# BPF.net
KiCad netlist of a schematic drawn in EAGLE
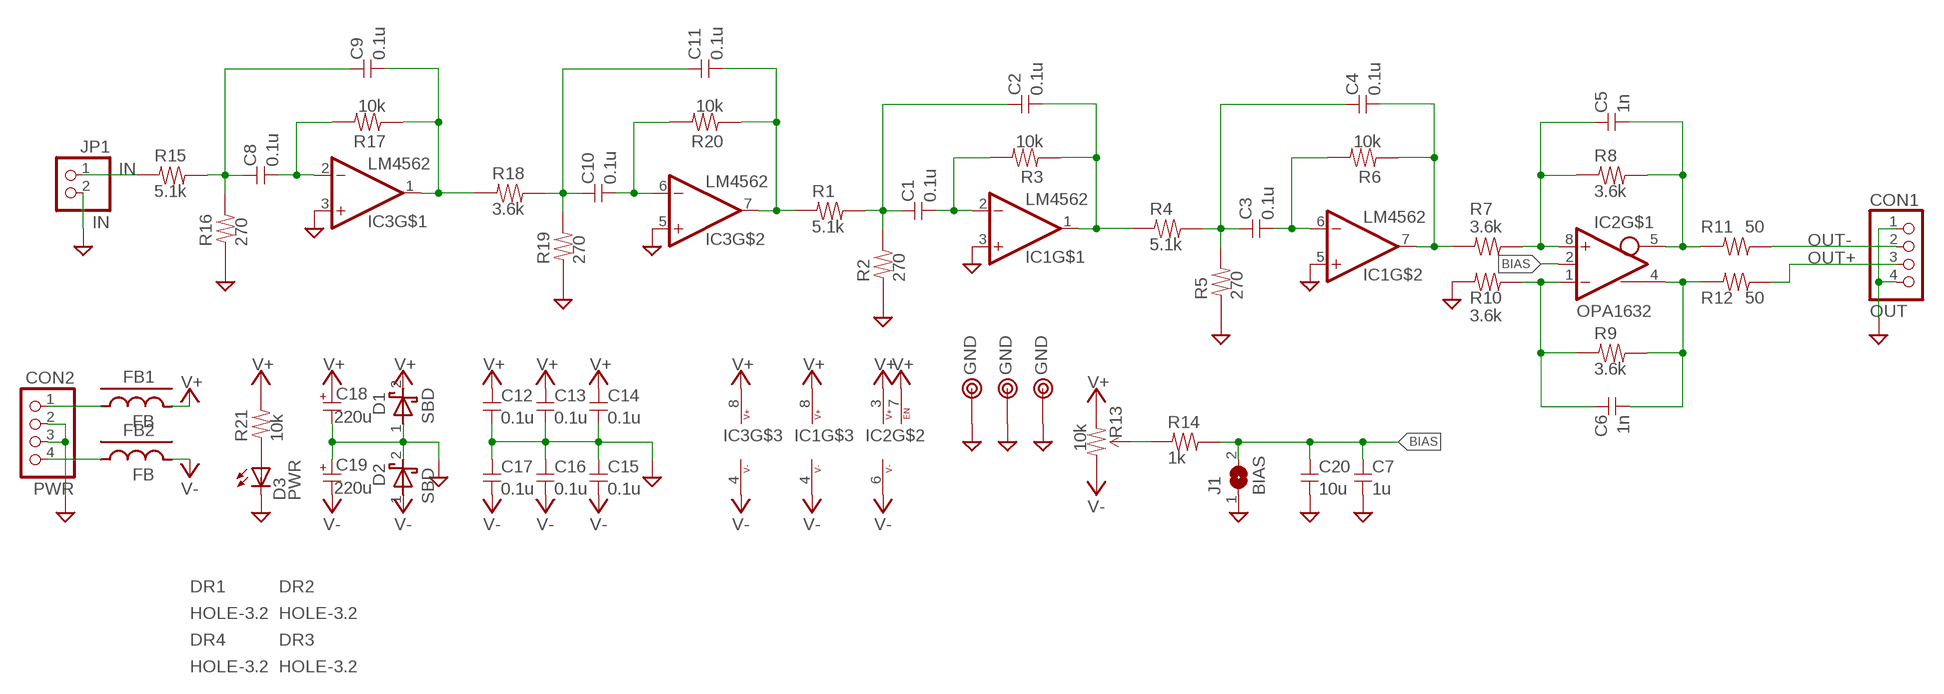
[diagram p0: schematic, sheet 1]

(export (version "E")
  (design (tool "Eeschema 10.0.6"))
  (components
    (comp (ref "C1")
      (value "0.1u")
      (footprint "eagle-import:C050W")
      (libsource (lib "eagle-import") (part "C-5W"))
    )
    (comp (ref "C2")
      (value "0.1u")
      (footprint "eagle-import:C050W")
      (libsource (lib "eagle-import") (part "C-5W"))
    )
    (comp (ref "C3")
      (value "0.1u")
      (footprint "eagle-import:C050W")
      (libsource (lib "eagle-import") (part "C-5W"))
    )
    (comp (ref "C4")
      (value "0.1u")
      (footprint "eagle-import:C050W")
      (libsource (lib "eagle-import") (part "C-5W"))
    )
    (comp (ref "C5")
      (value "1n")
      (footprint "eagle-import:2012")
      (libsource (lib "eagle-import") (part "C-2012"))
    )
    (comp (ref "C6")
      (value "1n")
      (footprint "eagle-import:2012")
      (libsource (lib "eagle-import") (part "C-2012"))
    )
    (comp (ref "C7")
      (value "1u")
      (footprint "eagle-import:1608C")
      (libsource (lib "eagle-import") (part "C-1608"))
    )
    (comp (ref "C8")
      (value "0.1u")
      (footprint "eagle-import:C050W")
      (libsource (lib "eagle-import") (part "C-5W"))
    )
    (comp (ref "C9")
      (value "0.1u")
      (footprint "eagle-import:C050W")
      (libsource (lib "eagle-import") (part "C-5W"))
    )
    (comp (ref "C10")
      (value "0.1u")
      (footprint "eagle-import:C050W")
      (libsource (lib "eagle-import") (part "C-5W"))
    )
    (comp (ref "C11")
      (value "0.1u")
      (footprint "eagle-import:C050W")
      (libsource (lib "eagle-import") (part "C-5W"))
    )
    (comp (ref "C12")
      (value "0.1u")
      (footprint "eagle-import:1608C")
      (libsource (lib "eagle-import") (part "C-1608"))
    )
    (comp (ref "C13")
      (value "0.1u")
      (footprint "eagle-import:1608C")
      (libsource (lib "eagle-import") (part "C-1608"))
    )
    (comp (ref "C14")
      (value "0.1u")
      (footprint "eagle-import:1608C")
      (libsource (lib "eagle-import") (part "C-1608"))
    )
    (comp (ref "C15")
      (value "0.1u")
      (footprint "eagle-import:1608C")
      (libsource (lib "eagle-import") (part "C-1608"))
    )
    (comp (ref "C16")
      (value "0.1u")
      (footprint "eagle-import:1608C")
      (libsource (lib "eagle-import") (part "C-1608"))
    )
    (comp (ref "C17")
      (value "0.1u")
      (footprint "eagle-import:1608C")
      (libsource (lib "eagle-import") (part "C-1608"))
    )
    (comp (ref "C18")
      (value "220u")
      (footprint "eagle-import:E2,5-8")
      (libsource (lib "eagle-import") (part "CPOLE2.5-8"))
    )
    (comp (ref "C19")
      (value "220u")
      (footprint "eagle-import:E2,5-8")
      (libsource (lib "eagle-import") (part "CPOLE2.5-8"))
    )
    (comp (ref "C20")
      (value "10u")
      (footprint "eagle-import:3216")
      (libsource (lib "eagle-import") (part "C-3216"))
    )
    (comp (ref "CON1")
      (value "OUT")
      (footprint "eagle-import:1X04")
      (libsource (lib "eagle-import") (part "PINHD-1X4-N"))
    )
    (comp (ref "CON2")
      (value "PWR")
      (footprint "eagle-import:1X04")
      (libsource (lib "eagle-import") (part "PINHD-1X4-N"))
    )
    (comp (ref "D1")
      (value "SBD")
      (footprint "eagle-import:SOD123")
      (libsource (lib "eagle-import") (part "SBD-1A2"))
    )
    (comp (ref "D2")
      (value "SBD")
      (footprint "eagle-import:SOD123")
      (libsource (lib "eagle-import") (part "SBD-1A2"))
    )
    (comp (ref "D3")
      (value "PWR")
      (footprint "eagle-import:D1608")
      (libsource (lib "eagle-import") (part "LED-SMD1608"))
    )
    (comp (ref "DR1")
      (value "HOLE-3.2")
      (footprint "eagle-import:HOLE_3.2")
      (libsource (lib "eagle-import") (part "HOLE-3.2"))
    )
    (comp (ref "DR2")
      (value "HOLE-3.2")
      (footprint "eagle-import:HOLE_3.2")
      (libsource (lib "eagle-import") (part "HOLE-3.2"))
    )
    (comp (ref "DR3")
      (value "HOLE-3.2")
      (footprint "eagle-import:HOLE_3.2")
      (libsource (lib "eagle-import") (part "HOLE-3.2"))
    )
    (comp (ref "DR4")
      (value "HOLE-3.2")
      (footprint "eagle-import:HOLE_3.2")
      (libsource (lib "eagle-import") (part "HOLE-3.2"))
    )
    (comp (ref "FB1")
      (value "FB")
      (footprint "eagle-import:2012-R")
      (libsource (lib "eagle-import") (part "FB-2012-FB"))
    )
    (comp (ref "FB2")
      (value "FB")
      (footprint "eagle-import:2012-R")
      (libsource (lib "eagle-import") (part "FB-2012-FB"))
    )
    (comp (ref "IC1")
      (value "LM4562")
      (footprint "eagle-import:SOP8")
      (libsource (lib "eagle-import") (part "OPA-2-SOP"))
    )
    (comp (ref "IC2")
      (value "OPA1632")
      (footprint "eagle-import:SOP8")
      (libsource (lib "eagle-import") (part "OPA-DIFF"))
    )
    (comp (ref "IC3")
      (value "LM4562")
      (footprint "eagle-import:SOP8")
      (libsource (lib "eagle-import") (part "OPA-2-SOP"))
    )
    (comp (ref "J1")
      (value "BIAS")
      (footprint "eagle-import:1608-J")
      (libsource (lib "eagle-import") (part "SJ-1608"))
    )
    (comp (ref "JP1")
      (value "IN")
      (footprint "eagle-import:1X02")
      (libsource (lib "eagle-import") (part "PINHD-1X2"))
    )
    (comp (ref "R1")
      (value "5.1k")
      (footprint "eagle-import:2012")
      (libsource (lib "eagle-import") (part "R-2012"))
    )
    (comp (ref "R2")
      (value "270")
      (footprint "eagle-import:2012")
      (libsource (lib "eagle-import") (part "R-2012"))
    )
    (comp (ref "R3")
      (value "10k")
      (footprint "eagle-import:2012")
      (libsource (lib "eagle-import") (part "R-2012"))
    )
    (comp (ref "R4")
      (value "5.1k")
      (footprint "eagle-import:2012")
      (libsource (lib "eagle-import") (part "R-2012"))
    )
    (comp (ref "R5")
      (value "270")
      (footprint "eagle-import:2012")
      (libsource (lib "eagle-import") (part "R-2012"))
    )
    (comp (ref "R6")
      (value "10k")
      (footprint "eagle-import:2012")
      (libsource (lib "eagle-import") (part "R-2012"))
    )
    (comp (ref "R7")
      (value "3.6k")
      (footprint "eagle-import:2012")
      (libsource (lib "eagle-import") (part "R-2012"))
    )
    (comp (ref "R8")
      (value "3.6k")
      (footprint "eagle-import:2012")
      (libsource (lib "eagle-import") (part "R-2012"))
    )
    (comp (ref "R9")
      (value "3.6k")
      (footprint "eagle-import:2012")
      (libsource (lib "eagle-import") (part "R-2012"))
    )
    (comp (ref "R10")
      (value "3.6k")
      (footprint "eagle-import:2012")
      (libsource (lib "eagle-import") (part "R-2012"))
    )
    (comp (ref "R11")
      (value "50")
      (footprint "eagle-import:1608")
      (libsource (lib "eagle-import") (part "R-1608"))
    )
    (comp (ref "R12")
      (value "50")
      (footprint "eagle-import:1608")
      (libsource (lib "eagle-import") (part "R-1608"))
    )
    (comp (ref "R13")
      (value "10k")
      (footprint "eagle-import:3296W")
      (libsource (lib "eagle-import") (part "R-VAL-3296W"))
    )
    (comp (ref "R14")
      (value "1k")
      (footprint "eagle-import:1608")
      (libsource (lib "eagle-import") (part "R-1608"))
    )
    (comp (ref "R15")
      (value "5.1k")
      (footprint "eagle-import:2012")
      (libsource (lib "eagle-import") (part "R-2012"))
    )
    (comp (ref "R16")
      (value "270")
      (footprint "eagle-import:2012")
      (libsource (lib "eagle-import") (part "R-2012"))
    )
    (comp (ref "R17")
      (value "10k")
      (footprint "eagle-import:2012")
      (libsource (lib "eagle-import") (part "R-2012"))
    )
    (comp (ref "R18")
      (value "3.6k")
      (footprint "eagle-import:2012")
      (libsource (lib "eagle-import") (part "R-2012"))
    )
    (comp (ref "R19")
      (value "270")
      (footprint "eagle-import:2012")
      (libsource (lib "eagle-import") (part "R-2012"))
    )
    (comp (ref "R20")
      (value "10k")
      (footprint "eagle-import:2012")
      (libsource (lib "eagle-import") (part "R-2012"))
    )
    (comp (ref "R21")
      (value "10k")
      (footprint "eagle-import:1608")
      (libsource (lib "eagle-import") (part "R-1608"))
    )
    (comp (ref "TP1")
      (value "GND")
      (footprint "eagle-import:TESTPIN")
      (libsource (lib "eagle-import") (part "TESTPIN"))
    )
    (comp (ref "TP2")
      (value "GND")
      (footprint "eagle-import:TESTPIN")
      (libsource (lib "eagle-import") (part "TESTPIN"))
    )
    (comp (ref "TP3")
      (value "GND")
      (footprint "eagle-import:TESTPIN")
      (libsource (lib "eagle-import") (part "TESTPIN"))
    )
  )
  (nets
    (net (code "1") (name "/IN") (class "Default")
      (node (ref "JP1") (pin "1") (pinfunction "1_1") (pintype "passive"))
      (node (ref "R15") (pin "1") (pinfunction "1_1") (pintype "passive"))
    )
    (net (code "2") (name "/OUT+") (class "Default")
      (node (ref "CON1") (pin "3") (pinfunction "3_3") (pintype "passive"))
      (node (ref "R12") (pin "2") (pinfunction "2_2") (pintype "passive"))
    )
    (net (code "3") (name "/OUT-") (class "Default")
      (node (ref "CON1") (pin "2") (pinfunction "2_2") (pintype "passive"))
      (node (ref "R11") (pin "2") (pinfunction "2_2") (pintype "passive"))
    )
    (net (code "4") (name "BIAS") (class "Default")
      (node (ref "C20") (pin "1") (pinfunction "1_1") (pintype "passive"))
      (node (ref "C7") (pin "1") (pinfunction "1_1") (pintype "passive"))
      (node (ref "IC2") (pin "2") (pinfunction "CM_2") (pintype "input"))
      (node (ref "J1") (pin "2") (pinfunction "2_2") (pintype "passive"))
      (node (ref "R14") (pin "2") (pinfunction "2_2") (pintype "passive"))
    )
    (net (code "5") (name "GND") (class "Default")
      (node (ref "C12") (pin "2") (pinfunction "2_2") (pintype "passive"))
      (node (ref "C13") (pin "2") (pinfunction "2_2") (pintype "passive"))
      (node (ref "C14") (pin "2") (pinfunction "2_2") (pintype "passive"))
      (node (ref "C15") (pin "1") (pinfunction "1_1") (pintype "passive"))
      (node (ref "C16") (pin "1") (pinfunction "1_1") (pintype "passive"))
      (node (ref "C17") (pin "1") (pinfunction "1_1") (pintype "passive"))
      (node (ref "C18") (pin "-") (pinfunction "2_-") (pintype "passive"))
      (node (ref "C19") (pin "+") (pinfunction "1_+") (pintype "passive"))
      (node (ref "C20") (pin "2") (pinfunction "2_2") (pintype "passive"))
      (node (ref "C7") (pin "2") (pinfunction "2_2") (pintype "passive"))
      (node (ref "CON1") (pin "1") (pinfunction "1_1") (pintype "passive"))
      (node (ref "CON1") (pin "4") (pinfunction "4_4") (pintype "passive"))
      (node (ref "CON2") (pin "2") (pinfunction "2_2") (pintype "passive"))
      (node (ref "CON2") (pin "3") (pinfunction "3_3") (pintype "passive"))
      (node (ref "D1") (pin "1") (pinfunction "A_1") (pintype "bidirectional"))
      (node (ref "D2") (pin "2") (pinfunction "K_2") (pintype "bidirectional"))
      (node (ref "D3") (pin "K") (pinfunction "K_K") (pintype "passive"))
      (node (ref "IC1") (pin "3") (pinfunction "+IN_3") (pintype "input"))
      (node (ref "IC1") (pin "5") (pinfunction "+IN_5") (pintype "input"))
      (node (ref "IC3") (pin "3") (pinfunction "+IN_3") (pintype "input"))
      (node (ref "IC3") (pin "5") (pinfunction "+IN_5") (pintype "input"))
      (node (ref "J1") (pin "1") (pinfunction "1_1") (pintype "passive"))
      (node (ref "JP1") (pin "2") (pinfunction "2_2") (pintype "passive"))
      (node (ref "R10") (pin "1") (pinfunction "1_1") (pintype "passive"))
      (node (ref "R16") (pin "1") (pinfunction "1_1") (pintype "passive"))
      (node (ref "R19") (pin "1") (pinfunction "1_1") (pintype "passive"))
      (node (ref "R2") (pin "1") (pinfunction "1_1") (pintype "passive"))
      (node (ref "R5") (pin "1") (pinfunction "1_1") (pintype "passive"))
      (node (ref "TP1") (pin "1") (pinfunction "1_1") (pintype "passive"))
      (node (ref "TP2") (pin "1") (pinfunction "1_1") (pintype "passive"))
      (node (ref "TP3") (pin "1") (pinfunction "1_1") (pintype "passive"))
    )
    (net (code "6") (name "Net-(C1-1-Pad3)") (class "Default")
      (node (ref "C1") (pin "1") (pinfunction "1_1") (pintype "passive"))
      (node (ref "C1") (pin "3") (pinfunction "1_3") (pintype "passive"))
      (node (ref "C2") (pin "1") (pinfunction "1_1") (pintype "passive"))
      (node (ref "C2") (pin "3") (pinfunction "1_3") (pintype "passive"))
      (node (ref "R1") (pin "2") (pinfunction "2_2") (pintype "passive"))
      (node (ref "R2") (pin "2") (pinfunction "2_2") (pintype "passive"))
    )
    (net (code "7") (name "Net-(C3-1-Pad3)") (class "Default")
      (node (ref "C3") (pin "1") (pinfunction "1_1") (pintype "passive"))
      (node (ref "C3") (pin "3") (pinfunction "1_3") (pintype "passive"))
      (node (ref "C4") (pin "1") (pinfunction "1_1") (pintype "passive"))
      (node (ref "C4") (pin "3") (pinfunction "1_3") (pintype "passive"))
      (node (ref "R4") (pin "2") (pinfunction "2_2") (pintype "passive"))
      (node (ref "R5") (pin "2") (pinfunction "2_2") (pintype "passive"))
    )
    (net (code "8") (name "Net-(C8-1-Pad3)") (class "Default")
      (node (ref "C8") (pin "1") (pinfunction "1_1") (pintype "passive"))
      (node (ref "C8") (pin "3") (pinfunction "1_3") (pintype "passive"))
      (node (ref "C9") (pin "1") (pinfunction "1_1") (pintype "passive"))
      (node (ref "C9") (pin "3") (pinfunction "1_3") (pintype "passive"))
      (node (ref "R15") (pin "2") (pinfunction "2_2") (pintype "passive"))
      (node (ref "R16") (pin "2") (pinfunction "2_2") (pintype "passive"))
    )
    (net (code "9") (name "Net-(C10-1-Pad3)") (class "Default")
      (node (ref "C10") (pin "1") (pinfunction "1_1") (pintype "passive"))
      (node (ref "C10") (pin "3") (pinfunction "1_3") (pintype "passive"))
      (node (ref "C11") (pin "1") (pinfunction "1_1") (pintype "passive"))
      (node (ref "C11") (pin "3") (pinfunction "1_3") (pintype "passive"))
      (node (ref "R18") (pin "2") (pinfunction "2_2") (pintype "passive"))
      (node (ref "R19") (pin "2") (pinfunction "2_2") (pintype "passive"))
    )
    (net (code "10") (name "Net-(CON2-Pad1)") (class "Default")
      (node (ref "CON2") (pin "1") (pinfunction "1_1") (pintype "passive"))
      (node (ref "FB1") (pin "1") (pinfunction "1_1") (pintype "passive"))
    )
    (net (code "11") (name "Net-(CON2-Pad4)") (class "Default")
      (node (ref "CON2") (pin "4") (pinfunction "4_4") (pintype "passive"))
      (node (ref "FB2") (pin "1") (pinfunction "1_1") (pintype "passive"))
    )
    (net (code "12") (name "Net-(D3-PadA)") (class "Default")
      (node (ref "D3") (pin "A") (pinfunction "A_A") (pintype "passive"))
      (node (ref "R21") (pin "1") (pinfunction "1_1") (pintype "passive"))
    )
    (net (code "13") (name "Net-(IC1A--IN)") (class "Default")
      (node (ref "C1") (pin "2") (pinfunction "2_2") (pintype "passive"))
      (node (ref "C1") (pin "4") (pinfunction "2_4") (pintype "passive"))
      (node (ref "IC1") (pin "2") (pinfunction "-IN_2") (pintype "input"))
      (node (ref "R3") (pin "2") (pinfunction "2_2") (pintype "passive"))
    )
    (net (code "14") (name "Net-(IC1A-OUT)") (class "Default")
      (node (ref "C2") (pin "2") (pinfunction "2_2") (pintype "passive"))
      (node (ref "C2") (pin "4") (pinfunction "2_4") (pintype "passive"))
      (node (ref "IC1") (pin "1") (pinfunction "OUT_1") (pintype "output"))
      (node (ref "R3") (pin "1") (pinfunction "1_1") (pintype "passive"))
      (node (ref "R4") (pin "1") (pinfunction "1_1") (pintype "passive"))
    )
    (net (code "15") (name "Net-(IC1B--IN)") (class "Default")
      (node (ref "C3") (pin "2") (pinfunction "2_2") (pintype "passive"))
      (node (ref "C3") (pin "4") (pinfunction "2_4") (pintype "passive"))
      (node (ref "IC1") (pin "6") (pinfunction "-IN_6") (pintype "input"))
      (node (ref "R6") (pin "2") (pinfunction "2_2") (pintype "passive"))
    )
    (net (code "16") (name "Net-(IC1B-OUT)") (class "Default")
      (node (ref "C4") (pin "2") (pinfunction "2_2") (pintype "passive"))
      (node (ref "C4") (pin "4") (pinfunction "2_4") (pintype "passive"))
      (node (ref "IC1") (pin "7") (pinfunction "OUT_7") (pintype "output"))
      (node (ref "R6") (pin "1") (pinfunction "1_1") (pintype "passive"))
      (node (ref "R7") (pin "1") (pinfunction "1_1") (pintype "passive"))
    )
    (net (code "17") (name "Net-(IC2A-+IN)") (class "Default")
      (node (ref "C5") (pin "1") (pinfunction "1_1") (pintype "passive"))
      (node (ref "IC2") (pin "8") (pinfunction "+IN_8") (pintype "input"))
      (node (ref "R7") (pin "2") (pinfunction "2_2") (pintype "passive"))
      (node (ref "R8") (pin "1") (pinfunction "1_1") (pintype "passive"))
    )
    (net (code "18") (name "Net-(IC2A-+OUT)") (class "Default")
      (node (ref "C6") (pin "2") (pinfunction "2_2") (pintype "passive"))
      (node (ref "IC2") (pin "4") (pinfunction "+OUT_4") (pintype "output"))
      (node (ref "R12") (pin "1") (pinfunction "1_1") (pintype "passive"))
      (node (ref "R9") (pin "2") (pinfunction "2_2") (pintype "passive"))
    )
    (net (code "19") (name "Net-(IC2A--IN)") (class "Default")
      (node (ref "C6") (pin "1") (pinfunction "1_1") (pintype "passive"))
      (node (ref "IC2") (pin "1") (pinfunction "-IN_1") (pintype "input"))
      (node (ref "R10") (pin "2") (pinfunction "2_2") (pintype "passive"))
      (node (ref "R9") (pin "1") (pinfunction "1_1") (pintype "passive"))
    )
    (net (code "20") (name "Net-(IC2A--OUT)") (class "Default")
      (node (ref "C5") (pin "2") (pinfunction "2_2") (pintype "passive"))
      (node (ref "IC2") (pin "5") (pinfunction "-OUT_5") (pintype "output"))
      (node (ref "R11") (pin "1") (pinfunction "1_1") (pintype "passive"))
      (node (ref "R8") (pin "2") (pinfunction "2_2") (pintype "passive"))
    )
    (net (code "21") (name "Net-(IC3A--IN)") (class "Default")
      (node (ref "C8") (pin "2") (pinfunction "2_2") (pintype "passive"))
      (node (ref "C8") (pin "4") (pinfunction "2_4") (pintype "passive"))
      (node (ref "IC3") (pin "2") (pinfunction "-IN_2") (pintype "input"))
      (node (ref "R17") (pin "2") (pinfunction "2_2") (pintype "passive"))
    )
    (net (code "22") (name "Net-(IC3A-OUT)") (class "Default")
      (node (ref "C9") (pin "2") (pinfunction "2_2") (pintype "passive"))
      (node (ref "C9") (pin "4") (pinfunction "2_4") (pintype "passive"))
      (node (ref "IC3") (pin "1") (pinfunction "OUT_1") (pintype "output"))
      (node (ref "R17") (pin "1") (pinfunction "1_1") (pintype "passive"))
      (node (ref "R18") (pin "1") (pinfunction "1_1") (pintype "passive"))
    )
    (net (code "23") (name "Net-(IC3B--IN)") (class "Default")
      (node (ref "C10") (pin "2") (pinfunction "2_2") (pintype "passive"))
      (node (ref "C10") (pin "4") (pinfunction "2_4") (pintype "passive"))
      (node (ref "IC3") (pin "6") (pinfunction "-IN_6") (pintype "input"))
      (node (ref "R20") (pin "2") (pinfunction "2_2") (pintype "passive"))
    )
    (net (code "24") (name "Net-(IC3B-OUT)") (class "Default")
      (node (ref "C11") (pin "2") (pinfunction "2_2") (pintype "passive"))
      (node (ref "C11") (pin "4") (pinfunction "2_4") (pintype "passive"))
      (node (ref "IC3") (pin "7") (pinfunction "OUT_7") (pintype "output"))
      (node (ref "R1") (pin "1") (pinfunction "1_1") (pintype "passive"))
      (node (ref "R20") (pin "1") (pinfunction "1_1") (pintype "passive"))
    )
    (net (code "25") (name "Net-(R13-Pad2)") (class "Default")
      (node (ref "R13") (pin "2") (pinfunction "2_2") (pintype "passive"))
      (node (ref "R14") (pin "1") (pinfunction "1_1") (pintype "passive"))
    )
    (net (code "26") (name "V+") (class "Default")
      (node (ref "C12") (pin "1") (pinfunction "1_1") (pintype "passive"))
      (node (ref "C13") (pin "1") (pinfunction "1_1") (pintype "passive"))
      (node (ref "C14") (pin "1") (pinfunction "1_1") (pintype "passive"))
      (node (ref "C18") (pin "+") (pinfunction "1_+") (pintype "passive"))
      (node (ref "D1") (pin "2") (pinfunction "K_2") (pintype "bidirectional"))
      (node (ref "FB1") (pin "2") (pinfunction "2_2") (pintype "passive"))
      (node (ref "IC1") (pin "8") (pinfunction "V+_8") (pintype "input"))
      (node (ref "IC2") (pin "3") (pinfunction "V+_3") (pintype "input"))
      (node (ref "IC2") (pin "7") (pinfunction "EN_7") (pintype "input"))
      (node (ref "IC3") (pin "8") (pinfunction "V+_8") (pintype "input"))
      (node (ref "R13") (pin "1") (pinfunction "1_1") (pintype "passive"))
      (node (ref "R21") (pin "2") (pinfunction "2_2") (pintype "passive"))
    )
    (net (code "27") (name "V-") (class "Default")
      (node (ref "C15") (pin "2") (pinfunction "2_2") (pintype "passive"))
      (node (ref "C16") (pin "2") (pinfunction "2_2") (pintype "passive"))
      (node (ref "C17") (pin "2") (pinfunction "2_2") (pintype "passive"))
      (node (ref "C19") (pin "-") (pinfunction "2_-") (pintype "passive"))
      (node (ref "D2") (pin "1") (pinfunction "A_1") (pintype "bidirectional"))
      (node (ref "FB2") (pin "2") (pinfunction "2_2") (pintype "passive"))
      (node (ref "IC1") (pin "4") (pinfunction "V-_4") (pintype "input"))
      (node (ref "IC2") (pin "6") (pinfunction "V-_6") (pintype "input"))
      (node (ref "IC3") (pin "4") (pinfunction "V-_4") (pintype "input"))
      (node (ref "R13") (pin "3") (pinfunction "3_3") (pintype "passive"))
    )
  )
)
